# MCU_STM32H743BI_POWER.net
KiCad netlist of a schematic drawn in Altium Designer
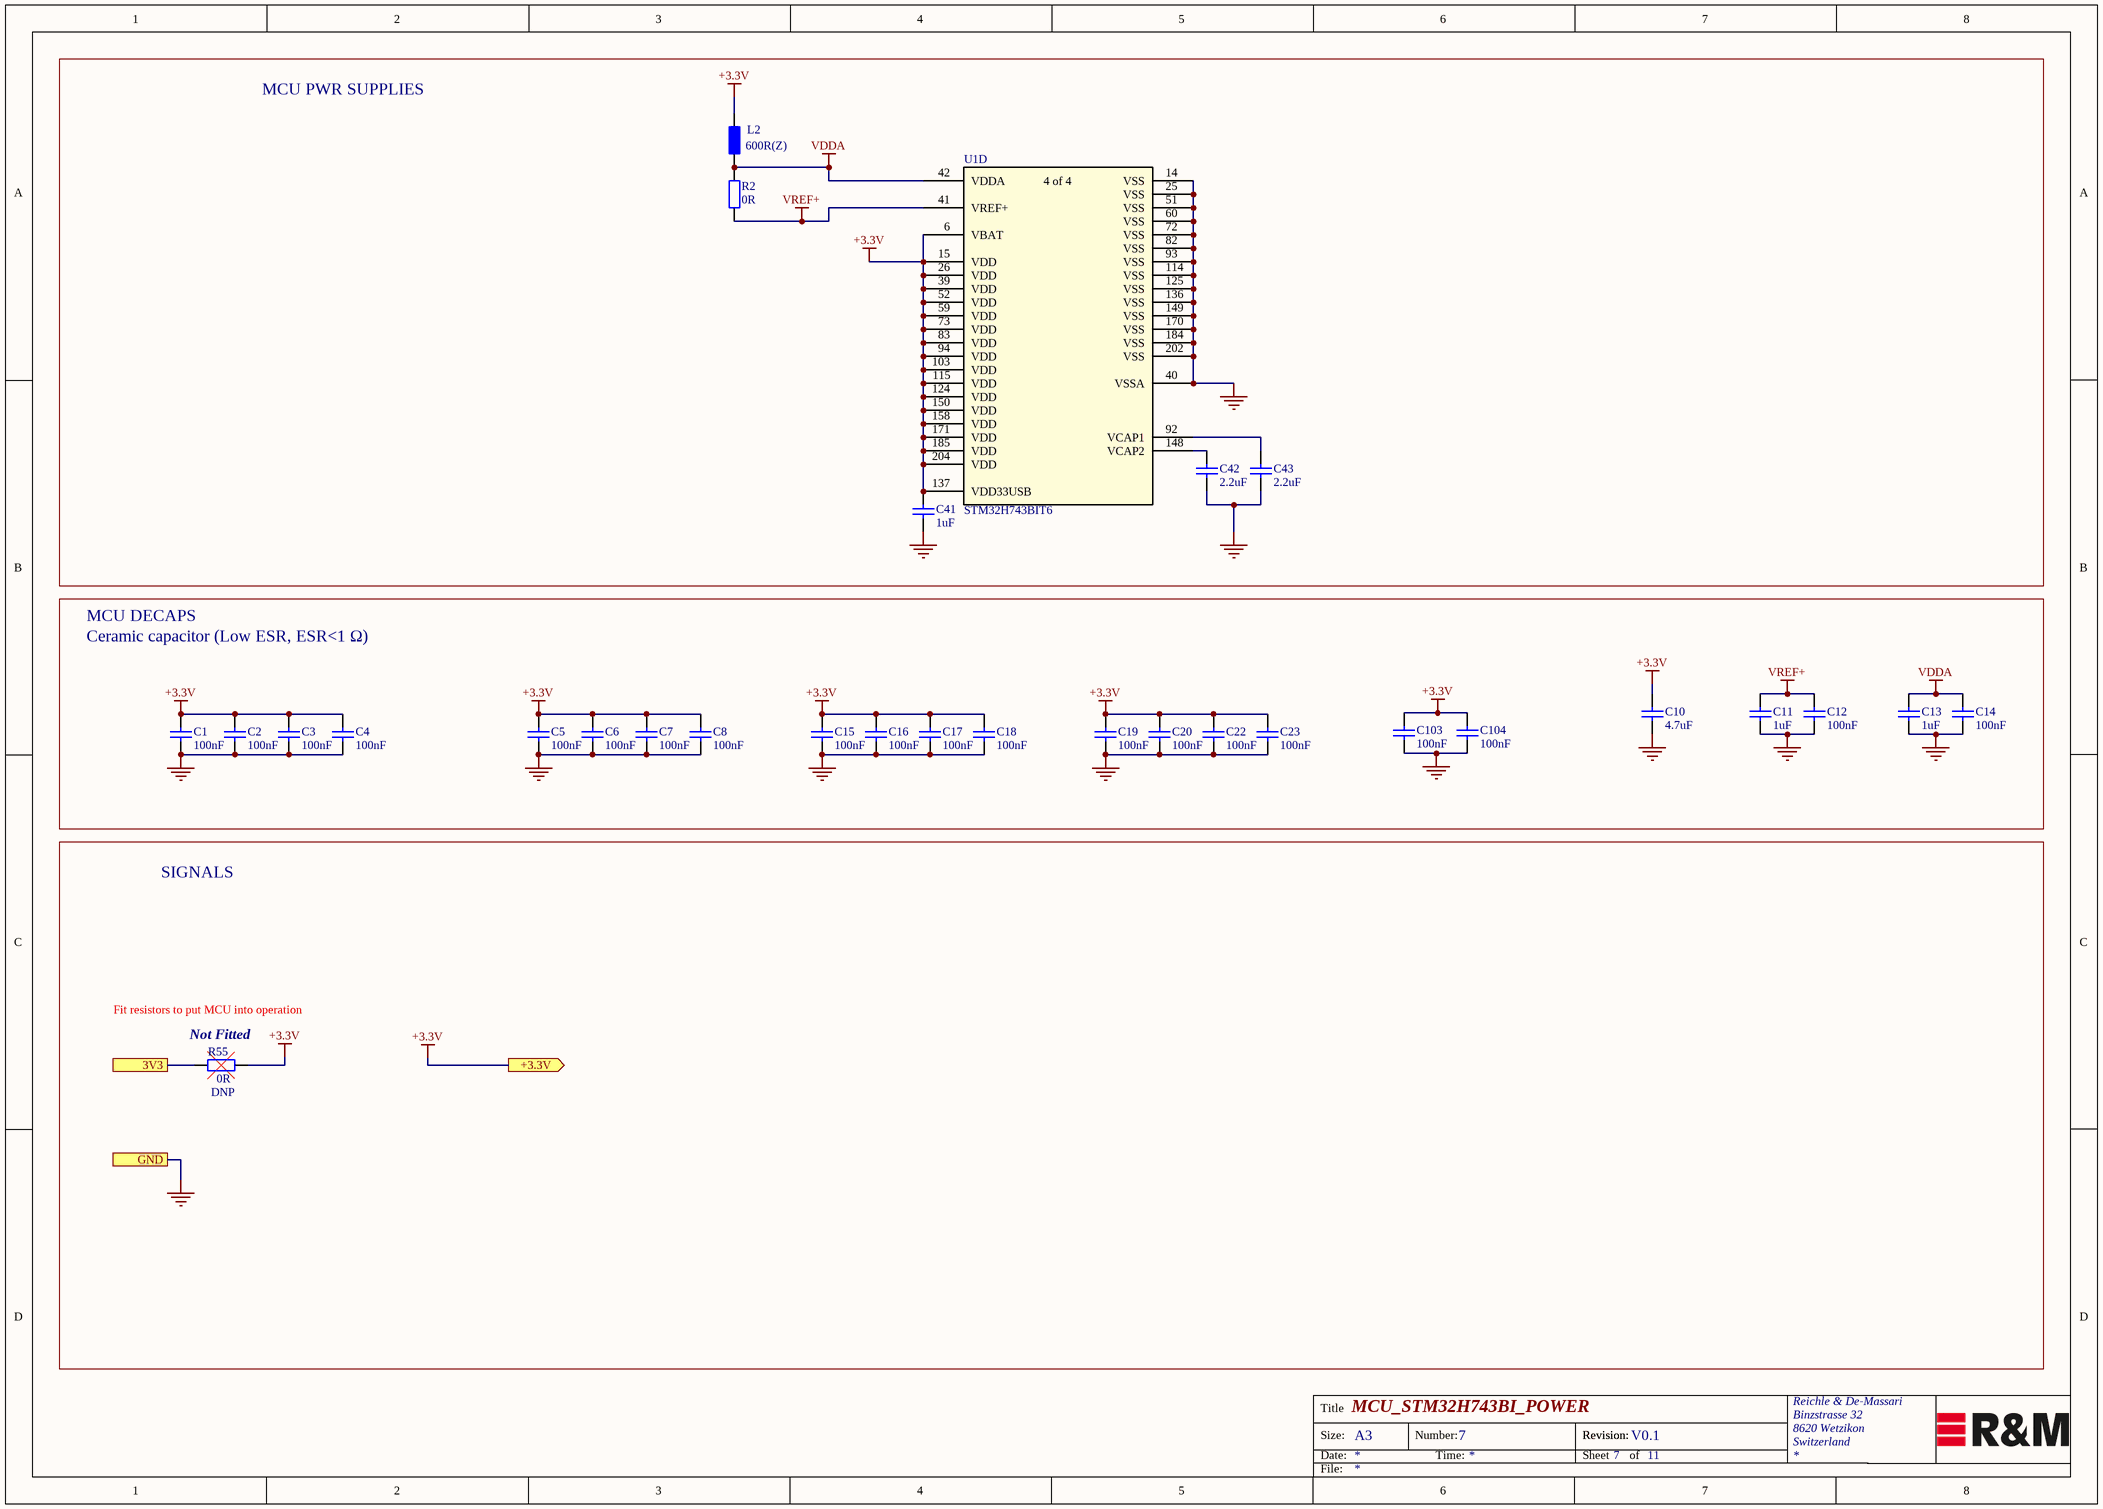
[diagram p0: MCU_STM32H743BI_POWER.SchDoc]

(export (version "E")
  (design (tool "Eeschema 10.0.6"))
  (components
    (comp (ref "C1")
      (value "100nF")
      (footprint "Ceramic Capacitor 0402 EIA")
      (description "0,1µF ±10% 10V Keramikkondensatoren X7R 0402 (1005 metrisch)")
      (fields (field (name "MANUFACTURER") "Samsung"))
      (libsource (lib "RDM_ALT_SCH") (part "Cap_100nF_0402_10V"))
    )
    (comp (ref "C2")
      (value "100nF")
      (footprint "Ceramic Capacitor 0402 EIA")
      (description "0,1µF ±10% 10V Keramikkondensatoren X7R 0402 (1005 metrisch)")
      (fields (field (name "MANUFACTURER") "Samsung"))
      (libsource (lib "RDM_ALT_SCH") (part "Cap_100nF_0402_10V"))
    )
    (comp (ref "C3")
      (value "100nF")
      (footprint "Ceramic Capacitor 0402 EIA")
      (description "0,1µF ±10% 10V Keramikkondensatoren X7R 0402 (1005 metrisch)")
      (fields (field (name "MANUFACTURER") "Samsung"))
      (libsource (lib "RDM_ALT_SCH") (part "Cap_100nF_0402_10V"))
    )
    (comp (ref "C4")
      (value "100nF")
      (footprint "Ceramic Capacitor 0402 EIA")
      (description "0,1µF ±10% 10V Keramikkondensatoren X7R 0402 (1005 metrisch)")
      (fields (field (name "MANUFACTURER") "Samsung"))
      (libsource (lib "RDM_ALT_SCH") (part "Cap_100nF_0402_10V"))
    )
    (comp (ref "C5")
      (value "100nF")
      (footprint "Ceramic Capacitor 0402 EIA")
      (description "0,1µF ±10% 10V Keramikkondensatoren X7R 0402 (1005 metrisch)")
      (fields (field (name "MANUFACTURER") "Samsung"))
      (libsource (lib "RDM_ALT_SCH") (part "Cap_100nF_0402_10V"))
    )
    (comp (ref "C6")
      (value "100nF")
      (footprint "Ceramic Capacitor 0402 EIA")
      (description "0,1µF ±10% 10V Keramikkondensatoren X7R 0402 (1005 metrisch)")
      (fields (field (name "MANUFACTURER") "Samsung"))
      (libsource (lib "RDM_ALT_SCH") (part "Cap_100nF_0402_10V"))
    )
    (comp (ref "C7")
      (value "100nF")
      (footprint "Ceramic Capacitor 0402 EIA")
      (description "0,1µF ±10% 10V Keramikkondensatoren X7R 0402 (1005 metrisch)")
      (fields (field (name "MANUFACTURER") "Samsung"))
      (libsource (lib "RDM_ALT_SCH") (part "Cap_100nF_0402_10V"))
    )
    (comp (ref "C8")
      (value "100nF")
      (footprint "Ceramic Capacitor 0402 EIA")
      (description "0,1µF ±10% 10V Keramikkondensatoren X7R 0402 (1005 metrisch)")
      (fields (field (name "MANUFACTURER") "Samsung"))
      (libsource (lib "RDM_ALT_SCH") (part "Cap_100nF_0402_10V"))
    )
    (comp (ref "C10")
      (value "4.7uF")
      (footprint "Ceramic Capacitor 0603 EIA")
      (description "4.7µF ±10% 10V Ceramic Capacitor X5R 0603 (1608 Metric)")
      (fields (field (name "TOLERANCE") "10%") (field (name "VOLTAGE") "10VDC"))
      (libsource (lib "RDM_ALT_SCH") (part "Cap_4.7uF_0603_10V"))
    )
    (comp (ref "C11")
      (value "1uF")
      (footprint "Ceramic Capacitor 0603 EIA")
      (description "1µF ±10% 25V Ceramic Capacitor X5R 0603 (1608 Metric)")
      (fields (field (name "TOLERANCE") "10%") (field (name "VOLTAGE") "25VDC"))
      (libsource (lib "RDM_ALT_SCH") (part "Cap_1uF_0603_25V"))
    )
    (comp (ref "C12")
      (value "100nF")
      (footprint "Ceramic Capacitor 0402 EIA")
      (description "0,1µF ±10% 10V Keramikkondensatoren X7R 0402 (1005 metrisch)")
      (fields (field (name "MANUFACTURER") "Samsung"))
      (libsource (lib "RDM_ALT_SCH") (part "Cap_100nF_0402_10V"))
    )
    (comp (ref "C13")
      (value "1uF")
      (footprint "Ceramic Capacitor 0603 EIA")
      (description "1µF ±10% 25V Ceramic Capacitor X5R 0603 (1608 Metric)")
      (fields (field (name "TOLERANCE") "10%") (field (name "VOLTAGE") "25VDC"))
      (libsource (lib "RDM_ALT_SCH") (part "Cap_1uF_0603_25V"))
    )
    (comp (ref "C14")
      (value "100nF")
      (footprint "Ceramic Capacitor 0402 EIA")
      (description "0,1µF ±10% 10V Keramikkondensatoren X7R 0402 (1005 metrisch)")
      (fields (field (name "MANUFACTURER") "Samsung"))
      (libsource (lib "RDM_ALT_SCH") (part "Cap_100nF_0402_10V"))
    )
    (comp (ref "C15")
      (value "100nF")
      (footprint "Ceramic Capacitor 0402 EIA")
      (description "0,1µF ±10% 10V Keramikkondensatoren X7R 0402 (1005 metrisch)")
      (fields (field (name "MANUFACTURER") "Samsung"))
      (libsource (lib "RDM_ALT_SCH") (part "Cap_100nF_0402_10V"))
    )
    (comp (ref "C16")
      (value "100nF")
      (footprint "Ceramic Capacitor 0402 EIA")
      (description "0,1µF ±10% 10V Keramikkondensatoren X7R 0402 (1005 metrisch)")
      (fields (field (name "MANUFACTURER") "Samsung"))
      (libsource (lib "RDM_ALT_SCH") (part "Cap_100nF_0402_10V"))
    )
    (comp (ref "C17")
      (value "100nF")
      (footprint "Ceramic Capacitor 0402 EIA")
      (description "0,1µF ±10% 10V Keramikkondensatoren X7R 0402 (1005 metrisch)")
      (fields (field (name "MANUFACTURER") "Samsung"))
      (libsource (lib "RDM_ALT_SCH") (part "Cap_100nF_0402_10V"))
    )
    (comp (ref "C18")
      (value "100nF")
      (footprint "Ceramic Capacitor 0402 EIA")
      (description "0,1µF ±10% 10V Keramikkondensatoren X7R 0402 (1005 metrisch)")
      (fields (field (name "MANUFACTURER") "Samsung"))
      (libsource (lib "RDM_ALT_SCH") (part "Cap_100nF_0402_10V"))
    )
    (comp (ref "C19")
      (value "100nF")
      (footprint "Ceramic Capacitor 0402 EIA")
      (description "0,1µF ±10% 10V Keramikkondensatoren X7R 0402 (1005 metrisch)")
      (fields (field (name "MANUFACTURER") "Samsung"))
      (libsource (lib "RDM_ALT_SCH") (part "Cap_100nF_0402_10V"))
    )
    (comp (ref "C20")
      (value "100nF")
      (footprint "Ceramic Capacitor 0402 EIA")
      (description "0,1µF ±10% 10V Keramikkondensatoren X7R 0402 (1005 metrisch)")
      (fields (field (name "MANUFACTURER") "Samsung"))
      (libsource (lib "RDM_ALT_SCH") (part "Cap_100nF_0402_10V"))
    )
    (comp (ref "C22")
      (value "100nF")
      (footprint "Ceramic Capacitor 0402 EIA")
      (description "0,1µF ±10% 10V Keramikkondensatoren X7R 0402 (1005 metrisch)")
      (fields (field (name "MANUFACTURER") "Samsung"))
      (libsource (lib "RDM_ALT_SCH") (part "Cap_100nF_0402_10V"))
    )
    (comp (ref "C23")
      (value "100nF")
      (footprint "Ceramic Capacitor 0402 EIA")
      (description "0,1µF ±10% 10V Keramikkondensatoren X7R 0402 (1005 metrisch)")
      (fields (field (name "MANUFACTURER") "Samsung"))
      (libsource (lib "RDM_ALT_SCH") (part "Cap_100nF_0402_10V"))
    )
    (comp (ref "C41")
      (value "1uF")
      (footprint "Ceramic Capacitor 0603 EIA")
      (description "1µF ±10% 25V Ceramic Capacitor X5R 0603 (1608 Metric)")
      (fields (field (name "TOLERANCE") "10%") (field (name "VOLTAGE") "25VDC"))
      (libsource (lib "RDM_ALT_SCH") (part "Cap_1uF_0603_25V"))
    )
    (comp (ref "C42")
      (value "2.2uF")
      (footprint "Ceramic Capacitor 0402 EIA")
      (description "2.2µF ±20% 25V Ceramic Capacitor X5R 0402 (1005 Metric)")
      (fields (field (name "TOLERANCE") "±20%") (field (name "VOLTAGE") "25VDC"))
      (libsource (lib "RDM_ALT_SCH") (part "Cap_2.2uF_0402_25V"))
    )
    (comp (ref "C43")
      (value "2.2uF")
      (footprint "Ceramic Capacitor 0402 EIA")
      (description "2.2µF ±20% 25V Ceramic Capacitor X5R 0402 (1005 Metric)")
      (fields (field (name "TOLERANCE") "±20%") (field (name "VOLTAGE") "25VDC"))
      (libsource (lib "RDM_ALT_SCH") (part "Cap_2.2uF_0402_25V"))
    )
    (comp (ref "C103")
      (value "100nF")
      (footprint "Ceramic Capacitor 0402 EIA")
      (description "0,1µF ±10% 10V Keramikkondensatoren X7R 0402 (1005 metrisch)")
      (fields (field (name "MANUFACTURER") "Samsung"))
      (libsource (lib "RDM_ALT_SCH") (part "Cap_100nF_0402_10V"))
    )
    (comp (ref "C104")
      (value "100nF")
      (footprint "Ceramic Capacitor 0402 EIA")
      (description "0,1µF ±10% 10V Keramikkondensatoren X7R 0402 (1005 metrisch)")
      (fields (field (name "MANUFACTURER") "Samsung"))
      (libsource (lib "RDM_ALT_SCH") (part "Cap_100nF_0402_10V"))
    )
    (comp (ref "L2")
      (value "600R(Z)")
      (footprint "Inductor 0603 EIA")
      (description "Ferritperlen MULTILYR CHP BD 0603 600OHMS 25%")
      (fields (field (name "TOLERANCE") "25%") (field (name "MANUFACTURER") "Taiyo Yuden"))
      (libsource (lib "RDM_ALT_SCH") (part "Ind_600R_0603"))
    )
    (comp (ref "R2")
      (value "0R")
      (footprint "Resistor 0603 EIA")
      (description "0 Ohms Jumper 0.1W, 1/10W Chip Resistor 0603 (1608 Metric) Moisture Resistant Thick Film")
      (fields (field (name "POWER") "0.1W, 1/10W") (field (name "MANUFACTURER") "Yageo"))
      (libsource (lib "RDM_ALT_SCH") (part "Res_0R_0603"))
    )
    (comp (ref "R55")
      (value "DNP")
      (footprint "Resistor 0805 EIA")
      (description "Resistor: do not populate")
      (fields (field (name "MANUFACTURER") "do not populate"))
      (libsource (lib "RDM_ALT_SCH") (part "Res_DNP_0805"))
    )
    (comp (ref "U1")
      (value "STM32H743BIT6")
      (footprint "LQFP208_STM32H743BITx")
      (description "ARM Cortex-M7 STM32H7 Mikrocontroller IC 32-Bit 480MHz 2MB (2M x 8) FLASH 208-LQFP (28x28)")
      (fields (field (name "VOLTAGE") "1,62V-3.6V") (field (name "MANUFACTURER") "STMicroelectronics"))
      (libsource (lib "RDM_ALT_SCH") (part "STM32H7x3BIT"))
    )
  )
  (nets
    (net (code "1") (name "+3.3V") (class "Default")
      (node (ref "C1") (pin "2") (pinfunction "2_2") (pintype "passive"))
      (node (ref "C10") (pin "2") (pinfunction "2_2") (pintype "passive"))
      (node (ref "C103") (pin "2") (pinfunction "2_2") (pintype "passive"))
      (node (ref "C104") (pin "2") (pinfunction "2_2") (pintype "passive"))
      (node (ref "C15") (pin "2") (pinfunction "2_2") (pintype "passive"))
      (node (ref "C16") (pin "2") (pinfunction "2_2") (pintype "passive"))
      (node (ref "C17") (pin "2") (pinfunction "2_2") (pintype "passive"))
      (node (ref "C18") (pin "2") (pinfunction "2_2") (pintype "passive"))
      (node (ref "C19") (pin "2") (pinfunction "2_2") (pintype "passive"))
      (node (ref "C2") (pin "2") (pinfunction "2_2") (pintype "passive"))
      (node (ref "C20") (pin "2") (pinfunction "2_2") (pintype "passive"))
      (node (ref "C22") (pin "2") (pinfunction "2_2") (pintype "passive"))
      (node (ref "C23") (pin "2") (pinfunction "2_2") (pintype "passive"))
      (node (ref "C3") (pin "2") (pinfunction "2_2") (pintype "passive"))
      (node (ref "C4") (pin "2") (pinfunction "2_2") (pintype "passive"))
      (node (ref "C41") (pin "2") (pinfunction "2_2") (pintype "passive"))
      (node (ref "C5") (pin "2") (pinfunction "2_2") (pintype "passive"))
      (node (ref "C6") (pin "2") (pinfunction "2_2") (pintype "passive"))
      (node (ref "C7") (pin "2") (pinfunction "2_2") (pintype "passive"))
      (node (ref "C8") (pin "2") (pinfunction "2_2") (pintype "passive"))
      (node (ref "L2") (pin "1") (pinfunction "1_1") (pintype "passive"))
      (node (ref "R55") (pin "2") (pinfunction "2_2") (pintype "passive"))
      (node (ref "U1") (pin "103") (pinfunction "VDD_103") (pintype "passive"))
      (node (ref "U1") (pin "115") (pinfunction "VDD_115") (pintype "passive"))
      (node (ref "U1") (pin "124") (pinfunction "VDD_124") (pintype "passive"))
      (node (ref "U1") (pin "137") (pinfunction "VDD33USB_137") (pintype "passive"))
      (node (ref "U1") (pin "15") (pinfunction "VDD_15") (pintype "passive"))
      (node (ref "U1") (pin "150") (pinfunction "VDD_150") (pintype "passive"))
      (node (ref "U1") (pin "158") (pinfunction "VDD_158") (pintype "passive"))
      (node (ref "U1") (pin "171") (pinfunction "VDD_171") (pintype "passive"))
      (node (ref "U1") (pin "185") (pinfunction "VDD_185") (pintype "passive"))
      (node (ref "U1") (pin "204") (pinfunction "VDD_204") (pintype "passive"))
      (node (ref "U1") (pin "26") (pinfunction "VDD_26") (pintype "passive"))
      (node (ref "U1") (pin "39") (pinfunction "VDD_39") (pintype "passive"))
      (node (ref "U1") (pin "52") (pinfunction "VDD_52") (pintype "passive"))
      (node (ref "U1") (pin "59") (pinfunction "VDD_59") (pintype "passive"))
      (node (ref "U1") (pin "6") (pinfunction "VBAT_6") (pintype "passive"))
      (node (ref "U1") (pin "73") (pinfunction "VDD_73") (pintype "passive"))
      (node (ref "U1") (pin "83") (pinfunction "VDD_83") (pintype "passive"))
      (node (ref "U1") (pin "94") (pinfunction "VDD_94") (pintype "passive"))
    )
    (net (code "2") (name "/3V3") (class "Default")
      (node (ref "R55") (pin "1") (pinfunction "1_1") (pintype "passive"))
    )
    (net (code "3") (name "GND") (class "Default")
      (node (ref "C1") (pin "1") (pinfunction "1_1") (pintype "passive"))
      (node (ref "C10") (pin "1") (pinfunction "1_1") (pintype "passive"))
      (node (ref "C103") (pin "1") (pinfunction "1_1") (pintype "passive"))
      (node (ref "C104") (pin "1") (pinfunction "1_1") (pintype "passive"))
      (node (ref "C11") (pin "1") (pinfunction "1_1") (pintype "passive"))
      (node (ref "C12") (pin "1") (pinfunction "1_1") (pintype "passive"))
      (node (ref "C13") (pin "1") (pinfunction "1_1") (pintype "passive"))
      (node (ref "C14") (pin "1") (pinfunction "1_1") (pintype "passive"))
      (node (ref "C15") (pin "1") (pinfunction "1_1") (pintype "passive"))
      (node (ref "C16") (pin "1") (pinfunction "1_1") (pintype "passive"))
      (node (ref "C17") (pin "1") (pinfunction "1_1") (pintype "passive"))
      (node (ref "C18") (pin "1") (pinfunction "1_1") (pintype "passive"))
      (node (ref "C19") (pin "1") (pinfunction "1_1") (pintype "passive"))
      (node (ref "C2") (pin "1") (pinfunction "1_1") (pintype "passive"))
      (node (ref "C20") (pin "1") (pinfunction "1_1") (pintype "passive"))
      (node (ref "C22") (pin "1") (pinfunction "1_1") (pintype "passive"))
      (node (ref "C23") (pin "1") (pinfunction "1_1") (pintype "passive"))
      (node (ref "C3") (pin "1") (pinfunction "1_1") (pintype "passive"))
      (node (ref "C4") (pin "1") (pinfunction "1_1") (pintype "passive"))
      (node (ref "C41") (pin "1") (pinfunction "1_1") (pintype "passive"))
      (node (ref "C42") (pin "1") (pinfunction "1_1") (pintype "passive"))
      (node (ref "C43") (pin "1") (pinfunction "1_1") (pintype "passive"))
      (node (ref "C5") (pin "1") (pinfunction "1_1") (pintype "passive"))
      (node (ref "C6") (pin "1") (pinfunction "1_1") (pintype "passive"))
      (node (ref "C7") (pin "1") (pinfunction "1_1") (pintype "passive"))
      (node (ref "C8") (pin "1") (pinfunction "1_1") (pintype "passive"))
      (node (ref "U1") (pin "114") (pinfunction "VSS_114") (pintype "passive"))
      (node (ref "U1") (pin "125") (pinfunction "VSS_125") (pintype "passive"))
      (node (ref "U1") (pin "136") (pinfunction "VSS_136") (pintype "passive"))
      (node (ref "U1") (pin "14") (pinfunction "VSS_14") (pintype "passive"))
      (node (ref "U1") (pin "149") (pinfunction "VSS_149") (pintype "passive"))
      (node (ref "U1") (pin "170") (pinfunction "VSS_170") (pintype "passive"))
      (node (ref "U1") (pin "184") (pinfunction "VSS_184") (pintype "passive"))
      (node (ref "U1") (pin "202") (pinfunction "VSS_202") (pintype "passive"))
      (node (ref "U1") (pin "25") (pinfunction "VSS_25") (pintype "passive"))
      (node (ref "U1") (pin "40") (pinfunction "VSSA_40") (pintype "passive"))
      (node (ref "U1") (pin "51") (pinfunction "VSS_51") (pintype "passive"))
      (node (ref "U1") (pin "60") (pinfunction "VSS_60") (pintype "passive"))
      (node (ref "U1") (pin "72") (pinfunction "VSS_72") (pintype "passive"))
      (node (ref "U1") (pin "82") (pinfunction "VSS_82") (pintype "passive"))
      (node (ref "U1") (pin "93") (pinfunction "VSS_93") (pintype "passive"))
    )
    (net (code "4") (name "Net-(U1D-VCAP1)") (class "Default")
      (node (ref "C43") (pin "2") (pinfunction "2_2") (pintype "passive"))
      (node (ref "U1") (pin "92") (pinfunction "VCAP1_92") (pintype "power_in"))
    )
    (net (code "5") (name "Net-(U1D-VCAP2)") (class "Default")
      (node (ref "C42") (pin "2") (pinfunction "2_2") (pintype "passive"))
      (node (ref "U1") (pin "148") (pinfunction "VCAP2_148") (pintype "power_in"))
    )
    (net (code "6") (name "VDDA") (class "Default")
      (node (ref "C13") (pin "2") (pinfunction "2_2") (pintype "passive"))
      (node (ref "C14") (pin "2") (pinfunction "2_2") (pintype "passive"))
      (node (ref "L2") (pin "2") (pinfunction "2_2") (pintype "passive"))
      (node (ref "R2") (pin "1") (pinfunction "1_1") (pintype "passive"))
      (node (ref "U1") (pin "42") (pinfunction "VDDA_42") (pintype "power_in"))
    )
    (net (code "7") (name "VREF+") (class "Default")
      (node (ref "C11") (pin "2") (pinfunction "2_2") (pintype "passive"))
      (node (ref "C12") (pin "2") (pinfunction "2_2") (pintype "passive"))
      (node (ref "R2") (pin "2") (pinfunction "2_2") (pintype "passive"))
      (node (ref "U1") (pin "41") (pinfunction "VREF+_41") (pintype "power_in"))
    )
  )
)
